# Power_Input_Circuit.net
KiCad netlist of a schematic drawn in Altium Designer
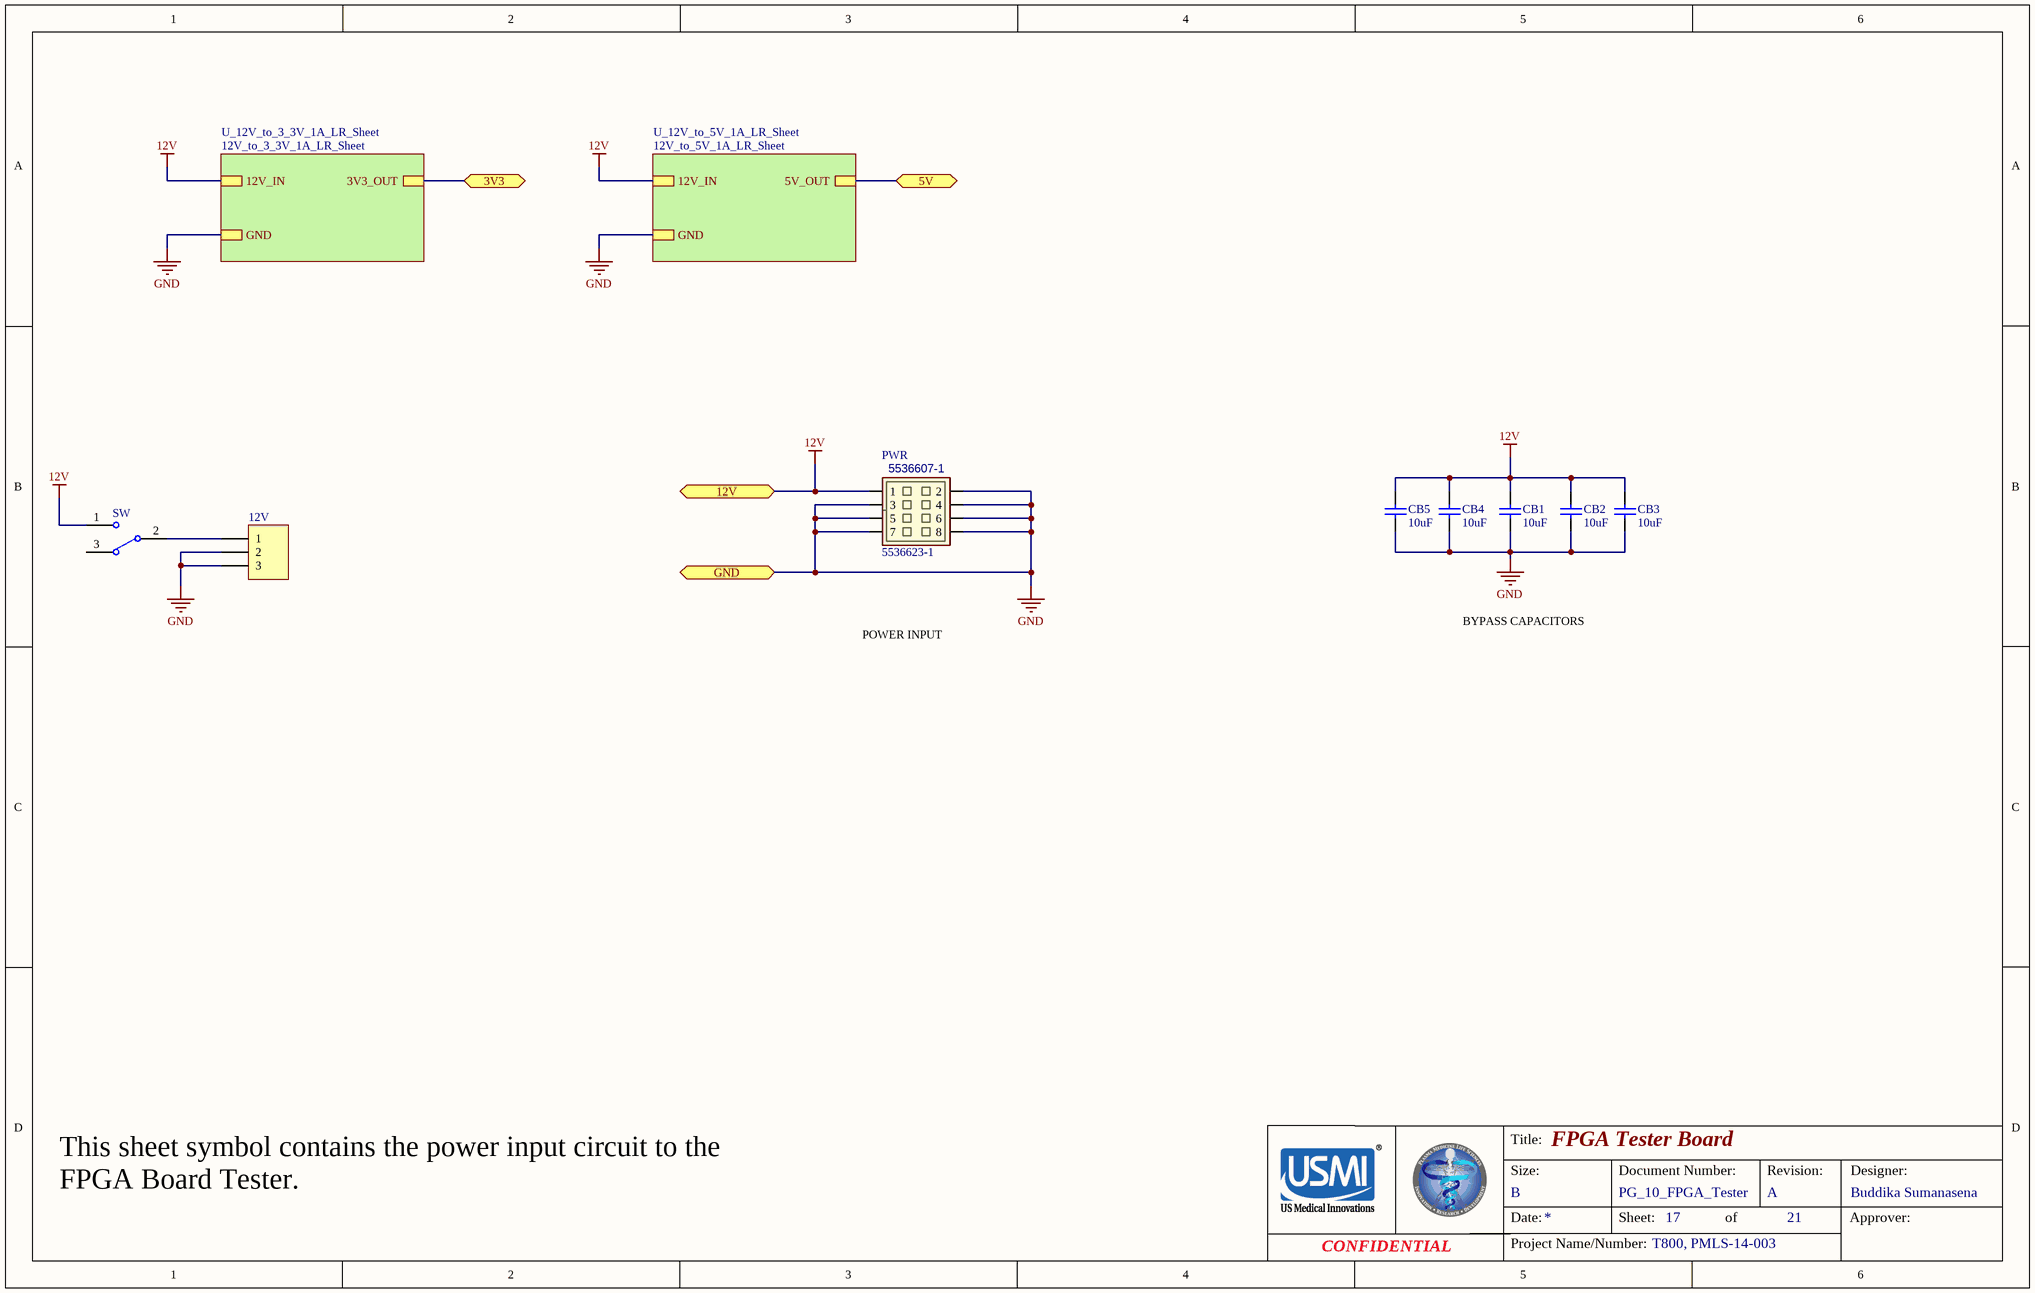
[diagram p0: Power_Input_Circuit.SchDoc]

(export (version "E")
  (design (tool "Eeschema 10.0.6"))
  (components
    (comp (ref "12V")
      (value "Header 3")
      (footprint "HDR1X3_12V")
      (description "Header, 3-Pin")
      (fields (field (name "PUBLISHER") "Altium Limited"))
      (libsource (lib "Buddika Miscellaneous Connectors") (part "Header 3"))
    )
    (comp (ref "CB1")
      (value "10uF")
      (footprint "1206c")
      (description "Capacitor")
      (fields (field (name "PUBLISHER") "Altium Limited"))
      (libsource (lib "Buddika Miscellaneous Devices") (part "Cap"))
    )
    (comp (ref "CB2")
      (value "10uF")
      (footprint "1206c")
      (description "Capacitor")
      (fields (field (name "PUBLISHER") "Altium Limited"))
      (libsource (lib "Buddika Miscellaneous Devices") (part "Cap"))
    )
    (comp (ref "CB3")
      (value "10uF")
      (footprint "1206c")
      (description "Capacitor")
      (fields (field (name "PUBLISHER") "Altium Limited"))
      (libsource (lib "Buddika Miscellaneous Devices") (part "Cap"))
    )
    (comp (ref "CB4")
      (value "10uF")
      (footprint "1206c")
      (description "Capacitor")
      (fields (field (name "PUBLISHER") "Altium Limited"))
      (libsource (lib "Buddika Miscellaneous Devices") (part "Cap"))
    )
    (comp (ref "CB5")
      (value "10uF")
      (footprint "1206c")
      (description "Capacitor")
      (fields (field (name "PUBLISHER") "Altium Limited"))
      (libsource (lib "Buddika Miscellaneous Devices") (part "Cap"))
    )
    (comp (ref "PWR")
      (value "5536623-1")
      (footprint "5536623-1")
      (description "TE Z-Pack 5536607-1")
      (libsource (lib "ES_LIB") (part "5536607-1"))
    )
    (comp (ref "SW")
      (value "SW")
      (footprint "CS12ANW03")
      (description "SPDT Subminiature Toggle Switch, Right Angle Mounting, Vertical Actuation")
      (fields (field (name "PUBLISHER") "Altium Limited"))
      (libsource (lib "Buddika Miscellaneous Devices") (part "SW-SPDT"))
    )
  )
  (nets
    (net (code "3") (name "12V") (class "Default")
      (node (ref "CB1") (pin "2") (pinfunction "2_2") (pintype "passive"))
      (node (ref "CB2") (pin "2") (pinfunction "2_2") (pintype "passive"))
      (node (ref "CB3") (pin "2") (pinfunction "2_2") (pintype "passive"))
      (node (ref "CB4") (pin "2") (pinfunction "2_2") (pintype "passive"))
      (node (ref "CB5") (pin "2") (pinfunction "2_2") (pintype "passive"))
      (node (ref "PWR") (pin "1") (pinfunction "1_1") (pintype "passive"))
      (node (ref "SW") (pin "1") (pinfunction "1_1") (pintype "passive"))
    )
    (net (code "4") (name "GND") (class "Default")
      (node (ref "12V") (pin "2") (pinfunction "2_2") (pintype "passive"))
      (node (ref "12V") (pin "3") (pinfunction "3_3") (pintype "passive"))
      (node (ref "CB1") (pin "1") (pinfunction "1_1") (pintype "passive"))
      (node (ref "CB2") (pin "1") (pinfunction "1_1") (pintype "passive"))
      (node (ref "CB3") (pin "1") (pinfunction "1_1") (pintype "passive"))
      (node (ref "CB4") (pin "1") (pinfunction "1_1") (pintype "passive"))
      (node (ref "CB5") (pin "1") (pinfunction "1_1") (pintype "passive"))
      (node (ref "PWR") (pin "2") (pinfunction "2_2") (pintype "passive"))
      (node (ref "PWR") (pin "3") (pinfunction "3_3") (pintype "passive"))
      (node (ref "PWR") (pin "4") (pinfunction "4_4") (pintype "passive"))
      (node (ref "PWR") (pin "5") (pinfunction "5_5") (pintype "passive"))
      (node (ref "PWR") (pin "6") (pinfunction "6_6") (pintype "passive"))
      (node (ref "PWR") (pin "7") (pinfunction "7_7") (pintype "passive"))
      (node (ref "PWR") (pin "8") (pinfunction "8_8") (pintype "passive"))
    )
    (net (code "5") (name "Net-(12V-Pad1)") (class "Default")
      (node (ref "12V") (pin "1") (pinfunction "1_1") (pintype "passive"))
      (node (ref "SW") (pin "2") (pinfunction "2_2") (pintype "passive"))
    )
    (net (code "6") (name "unconnected-(SW-Pad3)") (class "Default")
      (node (ref "SW") (pin "3") (pinfunction "3_3") (pintype "passive"))
    )
  )
)
